# CW1.net
KiCad netlist of a schematic drawn in EAGLE
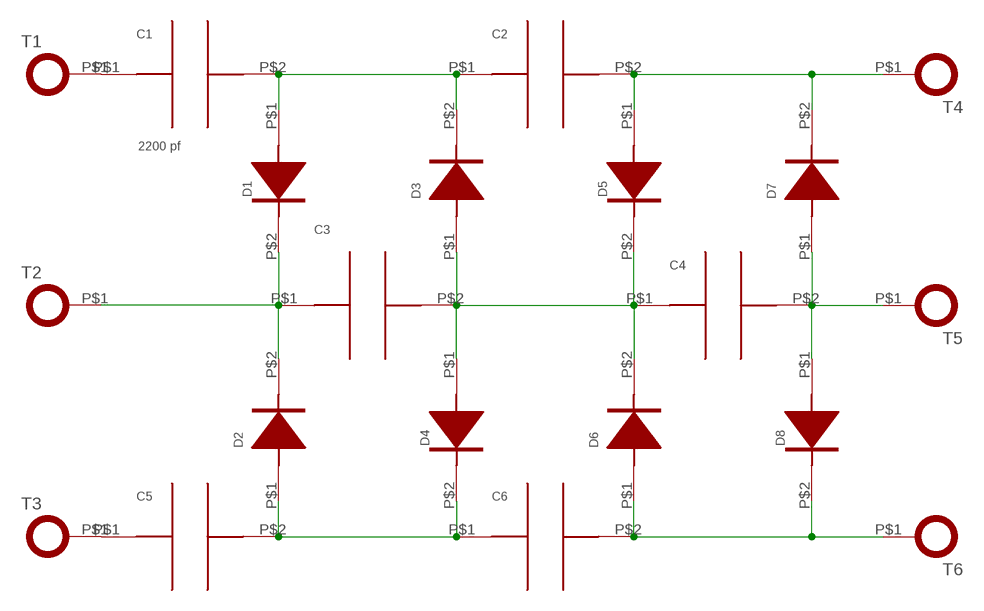
[diagram p0: schematic, sheet 1]

(export (version "E")
  (design (tool "Eeschema 10.0.6"))
  (components
    (comp (ref "C1")
      (value "2200 pf")
      (footprint "eagle-import:CAP_CT81_12")
      (libsource (lib "eagle-import") (part "HV_CAPACITOR_12MM"))
    )
    (comp (ref "C2")
      (value "HV_CAPACITOR_12MM")
      (footprint "eagle-import:CAP_CT81_12")
      (libsource (lib "eagle-import") (part "HV_CAPACITOR_12MM"))
    )
    (comp (ref "C3")
      (value "HV_CAPACITOR_12MM")
      (footprint "eagle-import:CAP_CT81_12")
      (libsource (lib "eagle-import") (part "HV_CAPACITOR_12MM"))
    )
    (comp (ref "C4")
      (value "HV_CAPACITOR_12MM")
      (footprint "eagle-import:CAP_CT81_12")
      (libsource (lib "eagle-import") (part "HV_CAPACITOR_12MM"))
    )
    (comp (ref "C5")
      (value "HV_CAPACITOR_12MM")
      (footprint "eagle-import:CAP_CT81_12")
      (libsource (lib "eagle-import") (part "HV_CAPACITOR_12MM"))
    )
    (comp (ref "C6")
      (value "HV_CAPACITOR_12MM")
      (footprint "eagle-import:CAP_CT81_12")
      (libsource (lib "eagle-import") (part "HV_CAPACITOR_12MM"))
    )
    (comp (ref "D1")
      (value "DIODE_14MM")
      (footprint "eagle-import:DIODE_14")
      (libsource (lib "eagle-import") (part "DIODE_14MM"))
    )
    (comp (ref "D2")
      (value "DIODE_14MM")
      (footprint "eagle-import:DIODE_14")
      (libsource (lib "eagle-import") (part "DIODE_14MM"))
    )
    (comp (ref "D3")
      (value "DIODE_14MM")
      (footprint "eagle-import:DIODE_14")
      (libsource (lib "eagle-import") (part "DIODE_14MM"))
    )
    (comp (ref "D4")
      (value "DIODE_14MM")
      (footprint "eagle-import:DIODE_14")
      (libsource (lib "eagle-import") (part "DIODE_14MM"))
    )
    (comp (ref "D5")
      (value "DIODE_14MM")
      (footprint "eagle-import:DIODE_14")
      (libsource (lib "eagle-import") (part "DIODE_14MM"))
    )
    (comp (ref "D6")
      (value "DIODE_14MM")
      (footprint "eagle-import:DIODE_14")
      (libsource (lib "eagle-import") (part "DIODE_14MM"))
    )
    (comp (ref "D7")
      (value "DIODE_14MM")
      (footprint "eagle-import:DIODE_14")
      (libsource (lib "eagle-import") (part "DIODE_14MM"))
    )
    (comp (ref "D8")
      (value "DIODE_14MM")
      (footprint "eagle-import:DIODE_14")
      (libsource (lib "eagle-import") (part "DIODE_14MM"))
    )
    (comp (ref "T1")
      (value "TERMINAL_M6")
      (footprint "eagle-import:LUG_SQUARE_M6")
      (libsource (lib "eagle-import") (part "TERMINAL_M6"))
    )
    (comp (ref "T2")
      (value "TERMINAL_M6")
      (footprint "eagle-import:LUG_SQUARE_M6")
      (libsource (lib "eagle-import") (part "TERMINAL_M6"))
    )
    (comp (ref "T3")
      (value "TERMINAL_M6")
      (footprint "eagle-import:LUG_SQUARE_M6")
      (libsource (lib "eagle-import") (part "TERMINAL_M6"))
    )
    (comp (ref "T4")
      (value "TERMINAL_M6")
      (footprint "eagle-import:LUG_SQUARE_M6")
      (libsource (lib "eagle-import") (part "TERMINAL_M6"))
    )
    (comp (ref "T5")
      (value "TERMINAL_M6")
      (footprint "eagle-import:LUG_SQUARE_M6")
      (libsource (lib "eagle-import") (part "TERMINAL_M6"))
    )
    (comp (ref "T6")
      (value "TERMINAL_M6")
      (footprint "eagle-import:LUG_SQUARE_M6")
      (libsource (lib "eagle-import") (part "TERMINAL_M6"))
    )
  )
  (nets
    (net (code "1") (name "Net-(C1-PadP$1)") (class "Default")
      (node (ref "C1") (pin "P$1") (pinfunction "P$1_P$1") (pintype "passive"))
      (node (ref "T1") (pin "P$1") (pinfunction "P$1_P$1") (pintype "passive"))
    )
    (net (code "2") (name "Net-(C5-PadP$1)") (class "Default")
      (node (ref "C5") (pin "P$1") (pinfunction "P$1_P$1") (pintype "passive"))
      (node (ref "T3") (pin "P$1") (pinfunction "P$1_P$1") (pintype "passive"))
    )
    (net (code "3") (name "Net-(D1-ANODE)") (class "Default")
      (node (ref "C1") (pin "P$2") (pinfunction "P$2_P$2") (pintype "passive"))
      (node (ref "C2") (pin "P$1") (pinfunction "P$1_P$1") (pintype "passive"))
      (node (ref "D1") (pin "P$1") (pinfunction "ANODE_P$1") (pintype "passive"))
      (node (ref "D3") (pin "P$2") (pinfunction "CATHODE_P$2") (pintype "passive"))
    )
    (net (code "4") (name "Net-(D1-CATHODE)") (class "Default")
      (node (ref "C3") (pin "P$1") (pinfunction "P$1_P$1") (pintype "passive"))
      (node (ref "D1") (pin "P$2") (pinfunction "CATHODE_P$2") (pintype "passive"))
      (node (ref "D2") (pin "P$2") (pinfunction "CATHODE_P$2") (pintype "passive"))
      (node (ref "T2") (pin "P$1") (pinfunction "P$1_P$1") (pintype "passive"))
    )
    (net (code "5") (name "Net-(D2-ANODE)") (class "Default")
      (node (ref "C5") (pin "P$2") (pinfunction "P$2_P$2") (pintype "passive"))
      (node (ref "C6") (pin "P$1") (pinfunction "P$1_P$1") (pintype "passive"))
      (node (ref "D2") (pin "P$1") (pinfunction "ANODE_P$1") (pintype "passive"))
      (node (ref "D4") (pin "P$2") (pinfunction "CATHODE_P$2") (pintype "passive"))
    )
    (net (code "6") (name "Net-(D3-ANODE)") (class "Default")
      (node (ref "C3") (pin "P$2") (pinfunction "P$2_P$2") (pintype "passive"))
      (node (ref "C4") (pin "P$1") (pinfunction "P$1_P$1") (pintype "passive"))
      (node (ref "D3") (pin "P$1") (pinfunction "ANODE_P$1") (pintype "passive"))
      (node (ref "D4") (pin "P$1") (pinfunction "ANODE_P$1") (pintype "passive"))
      (node (ref "D5") (pin "P$2") (pinfunction "CATHODE_P$2") (pintype "passive"))
      (node (ref "D6") (pin "P$2") (pinfunction "CATHODE_P$2") (pintype "passive"))
    )
    (net (code "7") (name "Net-(D5-ANODE)") (class "Default")
      (node (ref "C2") (pin "P$2") (pinfunction "P$2_P$2") (pintype "passive"))
      (node (ref "D5") (pin "P$1") (pinfunction "ANODE_P$1") (pintype "passive"))
      (node (ref "D7") (pin "P$2") (pinfunction "CATHODE_P$2") (pintype "passive"))
      (node (ref "T4") (pin "P$1") (pinfunction "P$1_P$1") (pintype "passive"))
    )
    (net (code "8") (name "Net-(D6-ANODE)") (class "Default")
      (node (ref "C6") (pin "P$2") (pinfunction "P$2_P$2") (pintype "passive"))
      (node (ref "D6") (pin "P$1") (pinfunction "ANODE_P$1") (pintype "passive"))
      (node (ref "D8") (pin "P$2") (pinfunction "CATHODE_P$2") (pintype "passive"))
      (node (ref "T6") (pin "P$1") (pinfunction "P$1_P$1") (pintype "passive"))
    )
    (net (code "9") (name "Net-(D7-ANODE)") (class "Default")
      (node (ref "C4") (pin "P$2") (pinfunction "P$2_P$2") (pintype "passive"))
      (node (ref "D7") (pin "P$1") (pinfunction "ANODE_P$1") (pintype "passive"))
      (node (ref "D8") (pin "P$1") (pinfunction "ANODE_P$1") (pintype "passive"))
      (node (ref "T5") (pin "P$1") (pinfunction "P$1_P$1") (pintype "passive"))
    )
  )
)
